# SCH_BatteryProtection-Circuit-copy_2026-.net
KiCad netlist of a schematic drawn in EasyEDA
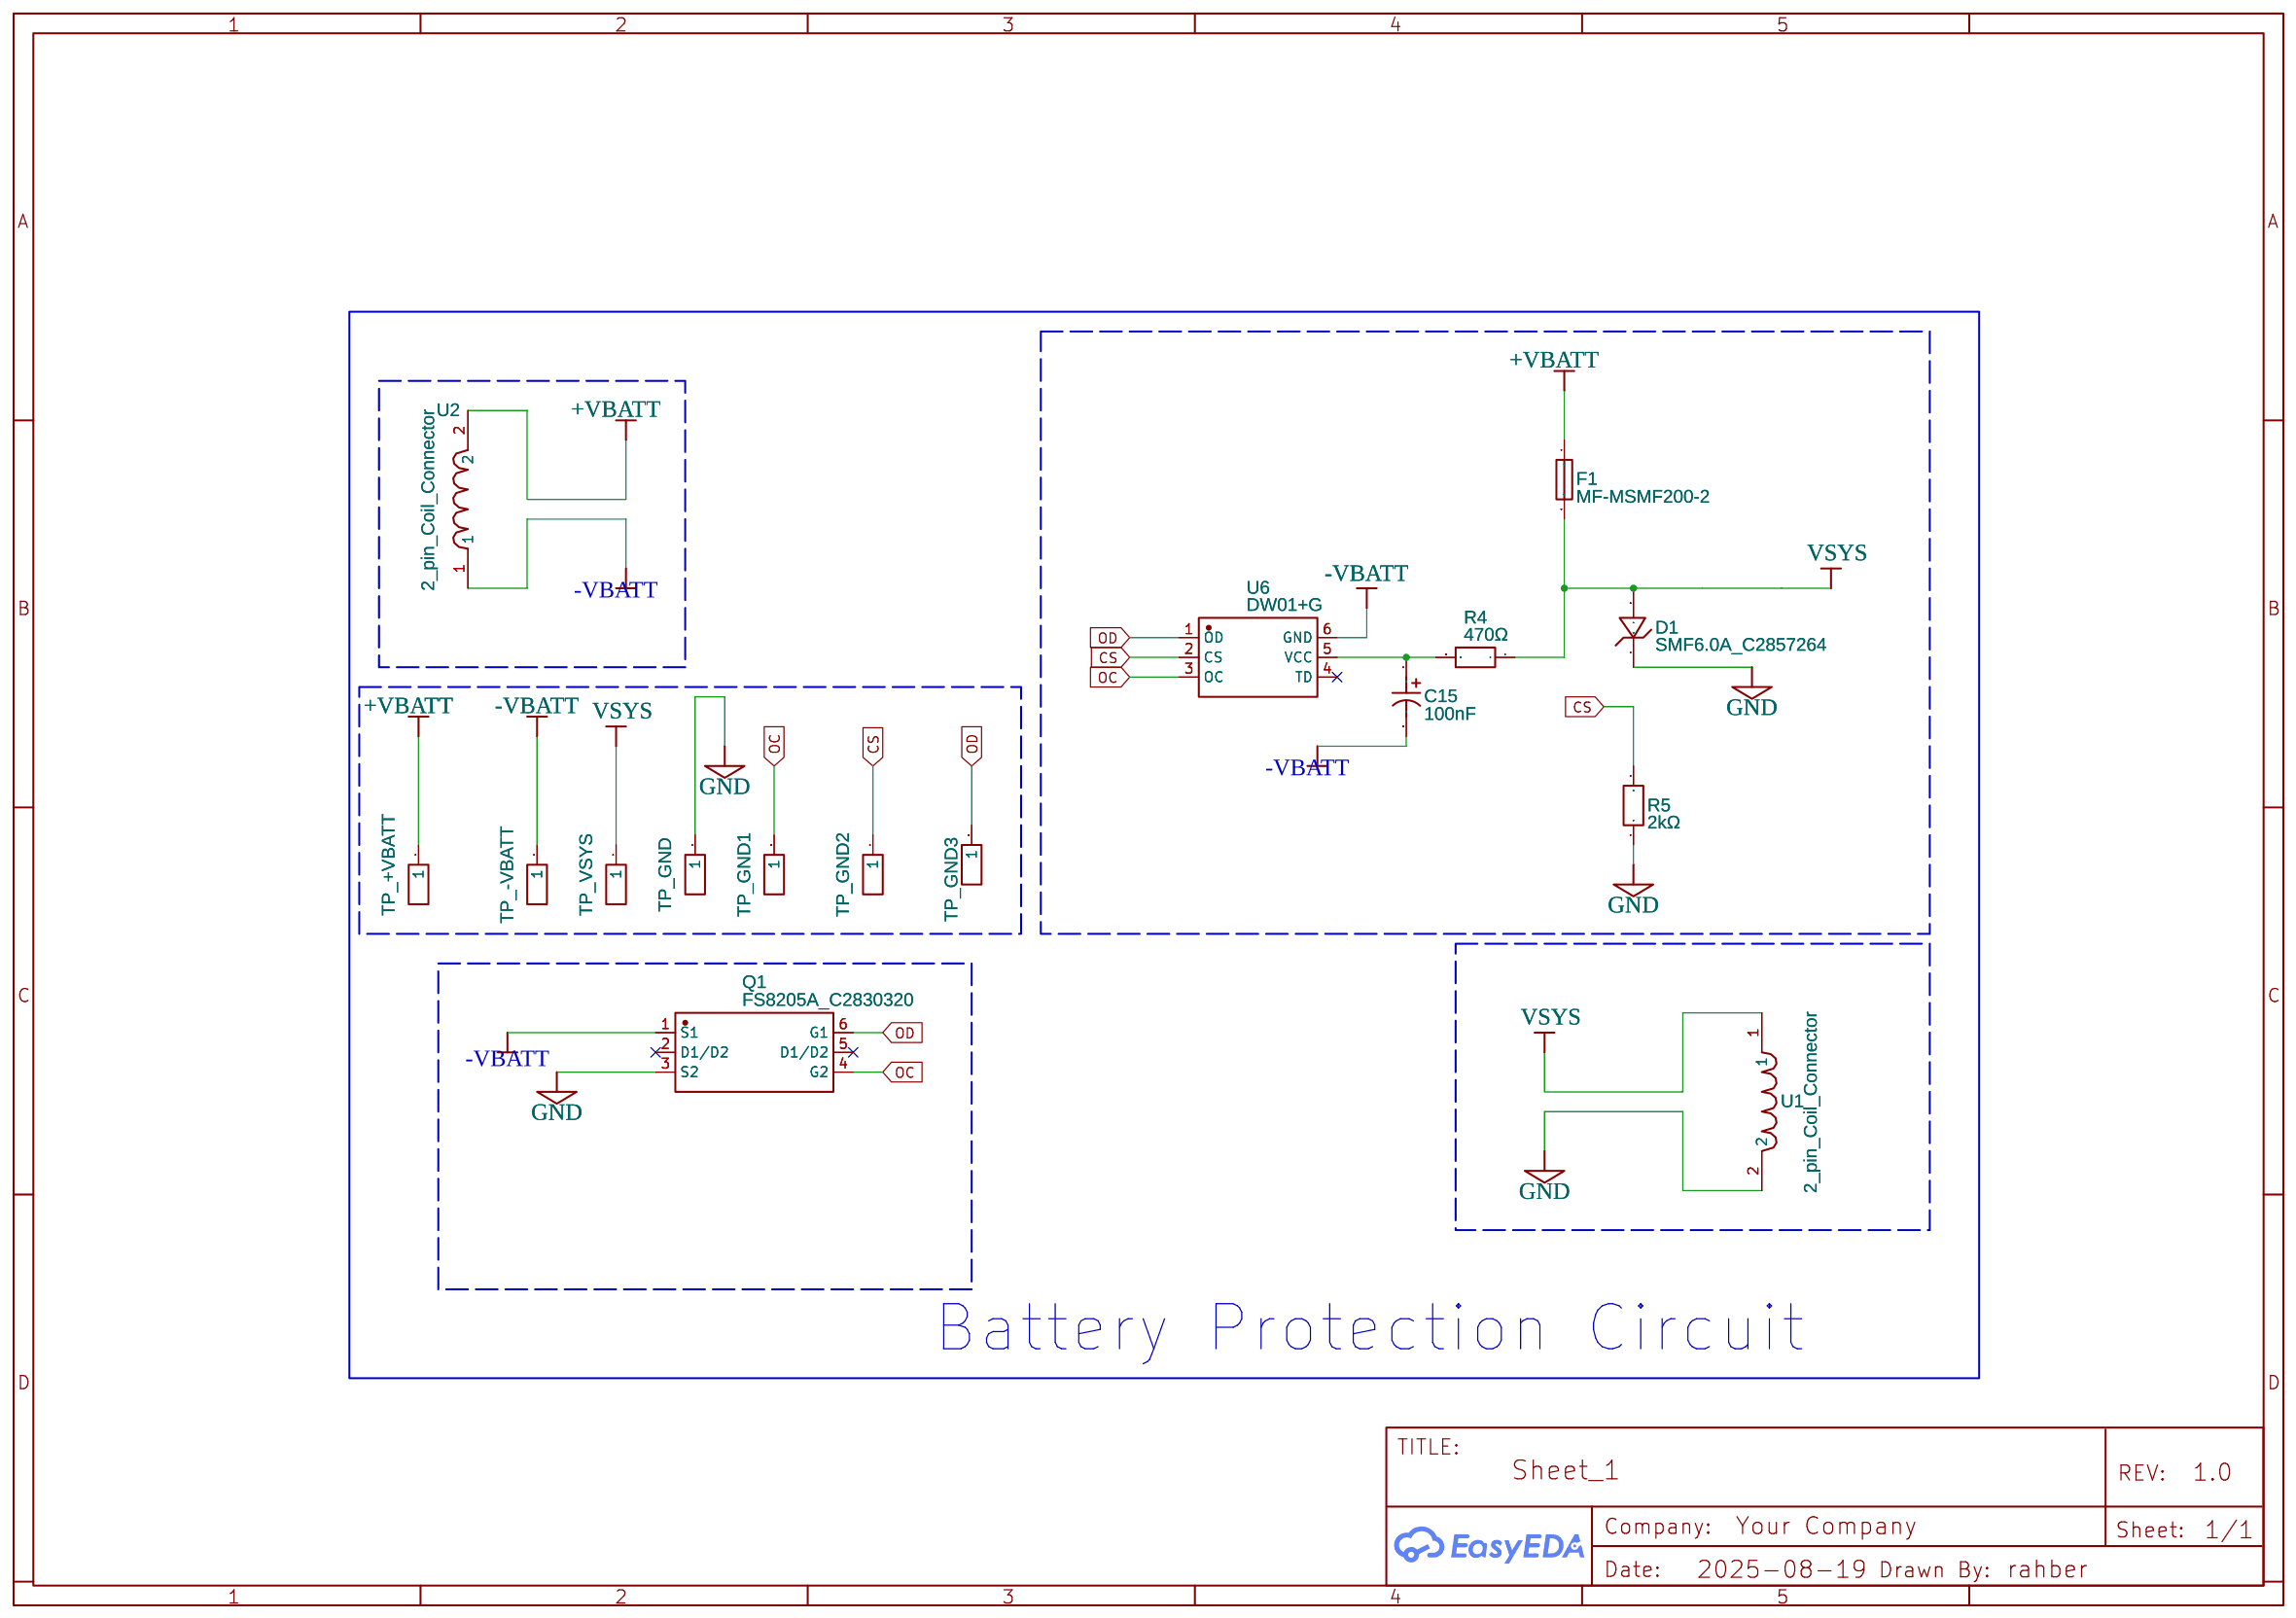
[diagram p0: schematic sheet]

(export (version "E")
  (design (tool "Eeschema 10.0.6"))
  (components
    (comp (ref "C15")
      (value "100nF")
      (fields (field (name "Manufacturer Part") "225RV0060") (field (name "Manufacturer") "KNSCHA(科尼盛)"))
      (libsource (lib "") (part "225RV0060"))
    )
    (comp (ref "D1")
      (value "SMF6.0A_C2857264")
      (fields (field (name "Manufacturer Part") "SMF6.0A") (field (name "Manufacturer") "JSMSEMI(杰盛微)"))
      (libsource (lib "") (part "SMF6.0A_C2857264"))
    )
    (comp (ref "F1")
      (value "MF-MSMF200-2")
      (fields (field (name "Manufacturer") "BOURNS"))
      (libsource (lib "") (part "MF-MSMF200-2"))
    )
    (comp (ref "Q1")
      (value "FS8205A_C2830320")
      (fields (field (name "Manufacturer Part") "FS8205A") (field (name "Manufacturer") "TECH PUBLIC(台舟)"))
      (libsource (lib "") (part "FS8205A_C2830320"))
    )
    (comp (ref "R4")
      (value "470Ω")
      (fields
        (field (name "Manufacturer Part") "TC0525B4700T5G")
        (field (name "Manufacturer") "UNI-ROYAL(厚声)")
      )
      (libsource (lib "") (part "TC0525B4700T5G"))
    )
    (comp (ref "R5")
      (value "2kΩ")
      (fields
        (field (name "Manufacturer Part") "TC0525B2001T5G")
        (field (name "Manufacturer") "UNI-ROYAL(厚声)")
      )
      (libsource (lib "") (part "TC0525B2001T5G"))
    )
    (comp (ref "TP_+VBATT") (value "HDR-M-2.54_1x1") (libsource (lib "") (part "HDR-M-2.54_1x1_1")))
    (comp (ref "TP_-VBATT") (value "HDR-M-2.54_1x1") (libsource (lib "") (part "HDR-M-2.54_1x1_2")))
    (comp (ref "TP_GND") (value "HDR-M-2.54_1x1") (libsource (lib "") (part "HDR-M-2.54_1x1")))
    (comp (ref "TP_GND1") (value "HDR-M-2.54_1x1") (libsource (lib "") (part "HDR-M-2.54_1x1")))
    (comp (ref "TP_GND2") (value "HDR-M-2.54_1x1") (libsource (lib "") (part "HDR-M-2.54_1x1")))
    (comp (ref "TP_GND3") (value "HDR-M-2.54_1x1") (libsource (lib "") (part "HDR-M-2.54_1x1")))
    (comp (ref "TP_VSYS") (value "HDR-M-2.54_1x1") (libsource (lib "") (part "HDR-M-2.54_1x1_3")))
    (comp (ref "U1")
      (value "2_pin_Coil_Connector")
      (fields
        (field (name "Manufacturer Part") "760308101141")
        (field (name "Manufacturer") "WURTH ELEKTRONIK")
      )
      (libsource (lib "") (part "2_pin_Coil_Connector_1"))
    )
    (comp (ref "U2")
      (value "2_pin_Coil_Connector")
      (fields
        (field (name "Manufacturer Part") "760308101141")
        (field (name "Manufacturer") "WURTH ELEKTRONIK")
      )
      (libsource (lib "") (part "2_pin_Coil_Connector"))
    )
    (comp (ref "U6")
      (value "DW01+G")
      (fields (field (name "Manufacturer") "FORTUNE(富晶)"))
      (libsource (lib "") (part "DW01+G"))
    )
  )
  (nets
    (net (code "1") (name "+VBATT") (class "Default")
      (node (ref "F1") (pin "1") (pinfunction "1_1") (pintype "unspecified"))
      (node (ref "TP_+VBATT") (pin "1") (pinfunction "1_1") (pintype "input"))
      (node (ref "U2") (pin "2") (pinfunction "2_2") (pintype "unspecified"))
    )
    (net (code "2") (name "-VBATT") (class "Default")
      (node (ref "C15") (pin "2") (pinfunction "2_2") (pintype "input"))
      (node (ref "Q1") (pin "1") (pinfunction "S1_1") (pintype "unspecified"))
      (node (ref "TP_-VBATT") (pin "1") (pinfunction "1_1") (pintype "input"))
      (node (ref "U2") (pin "1") (pinfunction "1_1") (pintype "unspecified"))
      (node (ref "U6") (pin "6") (pinfunction "GND_6") (pintype "unspecified"))
    )
    (net (code "3") (name "CS") (class "Default")
      (node (ref "R5") (pin "2") (pinfunction "2_2") (pintype "unspecified"))
      (node (ref "TP_GND2") (pin "1") (pinfunction "1_1") (pintype "input"))
      (node (ref "U6") (pin "2") (pinfunction "CS_2") (pintype "unspecified"))
    )
    (net (code "4") (name "GND") (class "Default")
      (node (ref "D1") (pin "1") (pinfunction "C_1") (pintype "unspecified"))
      (node (ref "Q1") (pin "3") (pinfunction "S2_3") (pintype "unspecified"))
      (node (ref "R5") (pin "1") (pinfunction "1_1") (pintype "unspecified"))
      (node (ref "TP_GND") (pin "1") (pinfunction "1_1") (pintype "input"))
      (node (ref "U1") (pin "2") (pinfunction "2_2") (pintype "unspecified"))
    )
    (net (code "5") (name "Net-(U6-VCC)") (class "Default")
      (node (ref "C15") (pin "1") (pinfunction "1_1") (pintype "input"))
      (node (ref "R4") (pin "2") (pinfunction "2_2") (pintype "unspecified"))
      (node (ref "U6") (pin "5") (pinfunction "VCC_5") (pintype "unspecified"))
    )
    (net (code "6") (name "OC") (class "Default")
      (node (ref "Q1") (pin "4") (pinfunction "G2_4") (pintype "unspecified"))
      (node (ref "TP_GND1") (pin "1") (pinfunction "1_1") (pintype "input"))
      (node (ref "U6") (pin "3") (pinfunction "OC_3") (pintype "unspecified"))
    )
    (net (code "7") (name "OD") (class "Default")
      (node (ref "Q1") (pin "6") (pinfunction "G1_6") (pintype "unspecified"))
      (node (ref "TP_GND3") (pin "1") (pinfunction "1_1") (pintype "input"))
      (node (ref "U6") (pin "1") (pinfunction "OD_1") (pintype "unspecified"))
    )
    (net (code "8") (name "VSYS") (class "Default")
      (node (ref "D1") (pin "2") (pinfunction "A_2") (pintype "unspecified"))
      (node (ref "F1") (pin "2") (pinfunction "2_2") (pintype "unspecified"))
      (node (ref "R4") (pin "1") (pinfunction "1_1") (pintype "unspecified"))
      (node (ref "TP_VSYS") (pin "1") (pinfunction "1_1") (pintype "input"))
      (node (ref "U1") (pin "1") (pinfunction "1_1") (pintype "unspecified"))
    )
    (net (code "9") (name "unconnected-(Q1-D1{slash}D2-Pad2)") (class "Default")
      (node (ref "Q1") (pin "2") (pinfunction "D1/D2_2") (pintype "unspecified+no_connect"))
    )
    (net (code "10") (name "unconnected-(Q1-D1{slash}D2-Pad5)") (class "Default")
      (node (ref "Q1") (pin "5") (pinfunction "D1/D2_5") (pintype "unspecified+no_connect"))
    )
    (net (code "11") (name "unconnected-(U6-TD-Pad4)") (class "Default")
      (node (ref "U6") (pin "4") (pinfunction "TD_4") (pintype "unspecified+no_connect"))
    )
  )
)
